# sr_lights.net
KiCad netlist of a schematic drawn in EAGLE
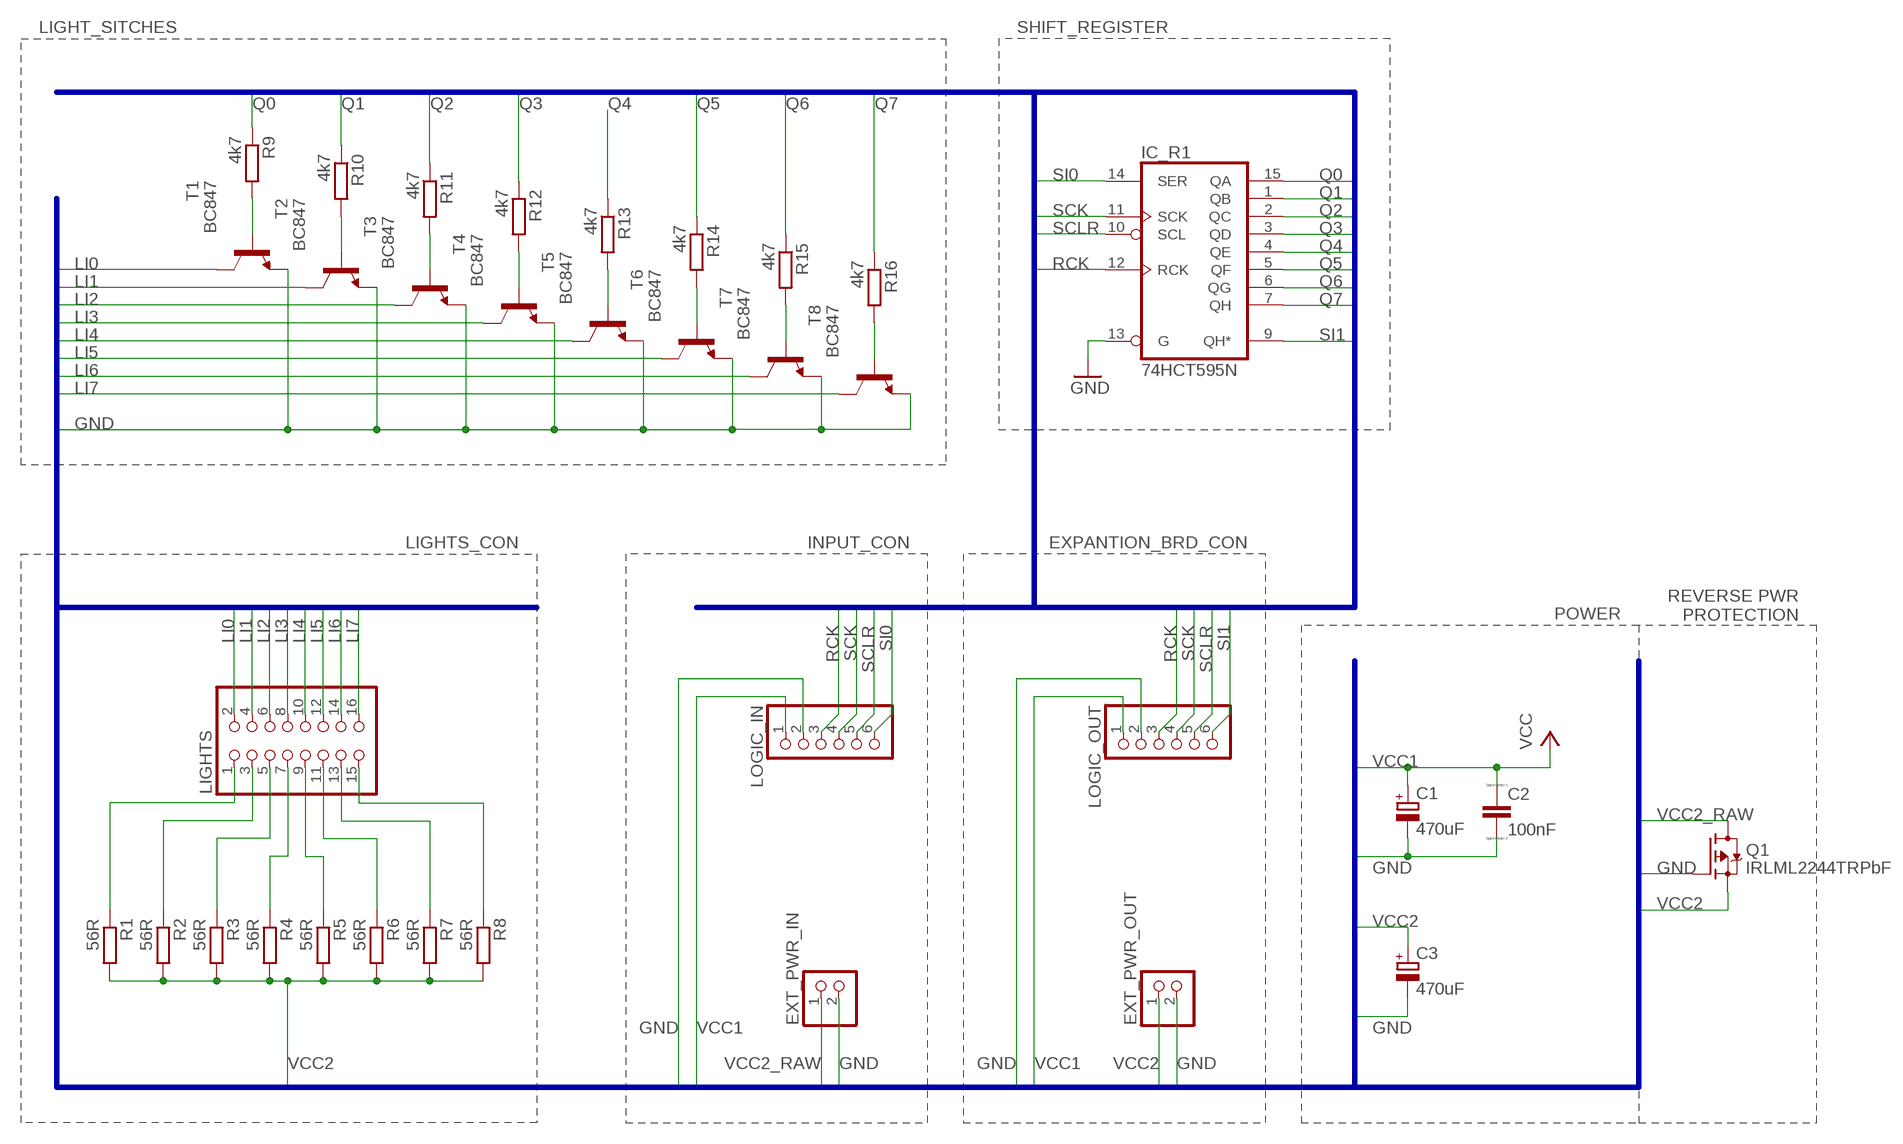
[diagram p0: schematic, sheet 1]

(export (version "E")
  (design (tool "Eeschema 10.0.6"))
  (components
    (comp (ref "C1")
      (value "470uF")
      (footprint "eagle-import:TT2D6")
      (libsource (lib "eagle-import") (part "CPOL-EUTT2D6"))
    )
    (comp (ref "C2")
      (value "100nF")
      (footprint "eagle-import:C0805")
      (libsource (lib "eagle-import") (part "C"))
    )
    (comp (ref "C3")
      (value "470uF")
      (footprint "eagle-import:TT2D6")
      (libsource (lib "eagle-import") (part "CPOL-EUTT2D6"))
    )
    (comp (ref "EXT_PWR_IN")
      (value "PINHD-1X2")
      (footprint "eagle-import:1X02")
      (libsource (lib "eagle-import") (part "PINHD-1X2"))
    )
    (comp (ref "EXT_PWR_OUT")
      (value "PINHD-1X2")
      (footprint "eagle-import:1X02")
      (libsource (lib "eagle-import") (part "PINHD-1X2"))
    )
    (comp (ref "IC_R1")
      (value "74HCT595N")
      (footprint "eagle-import:DIL16")
      (libsource (lib "eagle-import") (part "74595NHCT"))
    )
    (comp (ref "LIGHTS")
      (value "PINHD-2X8")
      (footprint "eagle-import:2X08")
      (libsource (lib "eagle-import") (part "PINHD-2X8"))
    )
    (comp (ref "LOGIC_IN")
      (value "PINHD-1X6")
      (footprint "eagle-import:1X06")
      (libsource (lib "eagle-import") (part "PINHD-1X6"))
    )
    (comp (ref "LOGIC_OUT")
      (value "PINHD-1X6")
      (footprint "eagle-import:1X06")
      (libsource (lib "eagle-import") (part "PINHD-1X6"))
    )
    (comp (ref "Q1")
      (value "IRLML2244TRPbF")
      (footprint "eagle-import:SOT23")
      (libsource (lib "eagle-import") (part "MOSFET-P-SOT23"))
    )
    (comp (ref "R1")
      (value "56R")
      (footprint "eagle-import:M0805")
      (libsource (lib "eagle-import") (part "R-EU_M0805"))
    )
    (comp (ref "R2")
      (value "56R")
      (footprint "eagle-import:M0805")
      (libsource (lib "eagle-import") (part "R-EU_M0805"))
    )
    (comp (ref "R3")
      (value "56R")
      (footprint "eagle-import:M0805")
      (libsource (lib "eagle-import") (part "R-EU_M0805"))
    )
    (comp (ref "R4")
      (value "56R")
      (footprint "eagle-import:M0805")
      (libsource (lib "eagle-import") (part "R-EU_M0805"))
    )
    (comp (ref "R5")
      (value "56R")
      (footprint "eagle-import:M0805")
      (libsource (lib "eagle-import") (part "R-EU_M0805"))
    )
    (comp (ref "R6")
      (value "56R")
      (footprint "eagle-import:M0805")
      (libsource (lib "eagle-import") (part "R-EU_M0805"))
    )
    (comp (ref "R7")
      (value "56R")
      (footprint "eagle-import:M0805")
      (libsource (lib "eagle-import") (part "R-EU_M0805"))
    )
    (comp (ref "R8")
      (value "56R")
      (footprint "eagle-import:M0805")
      (libsource (lib "eagle-import") (part "R-EU_M0805"))
    )
    (comp (ref "R9")
      (value "4k7")
      (footprint "eagle-import:M0805")
      (libsource (lib "eagle-import") (part "R-EU_M0805"))
    )
    (comp (ref "R10")
      (value "4k7")
      (footprint "eagle-import:M0805")
      (libsource (lib "eagle-import") (part "R-EU_M0805"))
    )
    (comp (ref "R11")
      (value "4k7")
      (footprint "eagle-import:M0805")
      (libsource (lib "eagle-import") (part "R-EU_M0805"))
    )
    (comp (ref "R12")
      (value "4k7")
      (footprint "eagle-import:M0805")
      (libsource (lib "eagle-import") (part "R-EU_M0805"))
    )
    (comp (ref "R13")
      (value "4k7")
      (footprint "eagle-import:M0805")
      (libsource (lib "eagle-import") (part "R-EU_M0805"))
    )
    (comp (ref "R14")
      (value "4k7")
      (footprint "eagle-import:M0805")
      (libsource (lib "eagle-import") (part "R-EU_M0805"))
    )
    (comp (ref "R15")
      (value "4k7")
      (footprint "eagle-import:M0805")
      (libsource (lib "eagle-import") (part "R-EU_M0805"))
    )
    (comp (ref "R16")
      (value "4k7")
      (footprint "eagle-import:M0805")
      (libsource (lib "eagle-import") (part "R-EU_M0805"))
    )
    (comp (ref "T1")
      (value "BC847")
      (footprint "eagle-import:SOT23")
      (libsource (lib "eagle-import") (part "BC847"))
    )
    (comp (ref "T2")
      (value "BC847")
      (footprint "eagle-import:SOT23")
      (libsource (lib "eagle-import") (part "BC847"))
    )
    (comp (ref "T3")
      (value "BC847")
      (footprint "eagle-import:SOT23")
      (libsource (lib "eagle-import") (part "BC847"))
    )
    (comp (ref "T4")
      (value "BC847")
      (footprint "eagle-import:SOT23")
      (libsource (lib "eagle-import") (part "BC847"))
    )
    (comp (ref "T5")
      (value "BC847")
      (footprint "eagle-import:SOT23")
      (libsource (lib "eagle-import") (part "BC847"))
    )
    (comp (ref "T6")
      (value "BC847")
      (footprint "eagle-import:SOT23")
      (libsource (lib "eagle-import") (part "BC847"))
    )
    (comp (ref "T7")
      (value "BC847")
      (footprint "eagle-import:SOT23")
      (libsource (lib "eagle-import") (part "BC847"))
    )
    (comp (ref "T8")
      (value "BC847")
      (footprint "eagle-import:SOT23")
      (libsource (lib "eagle-import") (part "BC847"))
    )
  )
  (nets
    (net (code "1") (name "/LI0") (class "Default")
      (node (ref "LIGHTS") (pin "2") (pinfunction "2_2") (pintype "passive"))
      (node (ref "T1") (pin "3") (pinfunction "C_3") (pintype "passive"))
    )
    (net (code "2") (name "/LI1") (class "Default")
      (node (ref "LIGHTS") (pin "4") (pinfunction "4_4") (pintype "passive"))
      (node (ref "T2") (pin "3") (pinfunction "C_3") (pintype "passive"))
    )
    (net (code "3") (name "/LI2") (class "Default")
      (node (ref "LIGHTS") (pin "6") (pinfunction "6_6") (pintype "passive"))
      (node (ref "T3") (pin "3") (pinfunction "C_3") (pintype "passive"))
    )
    (net (code "4") (name "/LI3") (class "Default")
      (node (ref "LIGHTS") (pin "8") (pinfunction "8_8") (pintype "passive"))
      (node (ref "T4") (pin "3") (pinfunction "C_3") (pintype "passive"))
    )
    (net (code "5") (name "/LI4") (class "Default")
      (node (ref "LIGHTS") (pin "10") (pinfunction "10_10") (pintype "passive"))
      (node (ref "T5") (pin "3") (pinfunction "C_3") (pintype "passive"))
    )
    (net (code "6") (name "/LI5") (class "Default")
      (node (ref "LIGHTS") (pin "12") (pinfunction "12_12") (pintype "passive"))
      (node (ref "T6") (pin "3") (pinfunction "C_3") (pintype "passive"))
    )
    (net (code "7") (name "/LI6") (class "Default")
      (node (ref "LIGHTS") (pin "14") (pinfunction "14_14") (pintype "passive"))
      (node (ref "T7") (pin "3") (pinfunction "C_3") (pintype "passive"))
    )
    (net (code "8") (name "/LI7") (class "Default")
      (node (ref "LIGHTS") (pin "16") (pinfunction "16_16") (pintype "passive"))
      (node (ref "T8") (pin "3") (pinfunction "C_3") (pintype "passive"))
    )
    (net (code "9") (name "/Q0") (class "Default")
      (node (ref "IC_R1") (pin "15") (pinfunction "QA_15") (pintype "tri_state"))
      (node (ref "R9") (pin "1") (pinfunction "1_1") (pintype "passive"))
    )
    (net (code "10") (name "/Q1") (class "Default")
      (node (ref "IC_R1") (pin "1") (pinfunction "QB_1") (pintype "tri_state"))
      (node (ref "R10") (pin "1") (pinfunction "1_1") (pintype "passive"))
    )
    (net (code "11") (name "/Q2") (class "Default")
      (node (ref "IC_R1") (pin "2") (pinfunction "QC_2") (pintype "tri_state"))
      (node (ref "R11") (pin "1") (pinfunction "1_1") (pintype "passive"))
    )
    (net (code "12") (name "/Q3") (class "Default")
      (node (ref "IC_R1") (pin "3") (pinfunction "QD_3") (pintype "tri_state"))
      (node (ref "R12") (pin "1") (pinfunction "1_1") (pintype "passive"))
    )
    (net (code "13") (name "/Q4") (class "Default")
      (node (ref "IC_R1") (pin "4") (pinfunction "QE_4") (pintype "tri_state"))
      (node (ref "R13") (pin "1") (pinfunction "1_1") (pintype "passive"))
    )
    (net (code "14") (name "/Q5") (class "Default")
      (node (ref "IC_R1") (pin "5") (pinfunction "QF_5") (pintype "tri_state"))
      (node (ref "R14") (pin "1") (pinfunction "1_1") (pintype "passive"))
    )
    (net (code "15") (name "/Q6") (class "Default")
      (node (ref "IC_R1") (pin "6") (pinfunction "QG_6") (pintype "tri_state"))
      (node (ref "R15") (pin "1") (pinfunction "1_1") (pintype "passive"))
    )
    (net (code "16") (name "/Q7") (class "Default")
      (node (ref "IC_R1") (pin "7") (pinfunction "QH_7") (pintype "tri_state"))
      (node (ref "R16") (pin "1") (pinfunction "1_1") (pintype "passive"))
    )
    (net (code "17") (name "/RCK") (class "Default")
      (node (ref "IC_R1") (pin "12") (pinfunction "RCK_12") (pintype "input"))
      (node (ref "LOGIC_IN") (pin "3") (pinfunction "3_3") (pintype "passive"))
      (node (ref "LOGIC_OUT") (pin "3") (pinfunction "3_3") (pintype "passive"))
    )
    (net (code "18") (name "/SCK") (class "Default")
      (node (ref "IC_R1") (pin "11") (pinfunction "SCK_11") (pintype "input"))
      (node (ref "LOGIC_IN") (pin "4") (pinfunction "4_4") (pintype "passive"))
      (node (ref "LOGIC_OUT") (pin "4") (pinfunction "4_4") (pintype "passive"))
    )
    (net (code "19") (name "/SCLR") (class "Default")
      (node (ref "IC_R1") (pin "10") (pinfunction "SCL_10") (pintype "input"))
      (node (ref "LOGIC_IN") (pin "5") (pinfunction "5_5") (pintype "passive"))
      (node (ref "LOGIC_OUT") (pin "5") (pinfunction "5_5") (pintype "passive"))
    )
    (net (code "20") (name "/SI0") (class "Default")
      (node (ref "IC_R1") (pin "14") (pinfunction "SER_14") (pintype "input"))
      (node (ref "LOGIC_IN") (pin "6") (pinfunction "6_6") (pintype "passive"))
    )
    (net (code "21") (name "/SI1") (class "Default")
      (node (ref "IC_R1") (pin "9") (pinfunction "QH*_9") (pintype "tri_state"))
      (node (ref "LOGIC_OUT") (pin "6") (pinfunction "6_6") (pintype "passive"))
    )
    (net (code "22") (name "/VCC2") (class "Default")
      (node (ref "C3") (pin "+") (pinfunction "+_+") (pintype "passive"))
      (node (ref "EXT_PWR_OUT") (pin "1") (pinfunction "1_1") (pintype "passive"))
      (node (ref "Q1") (pin "2") (pinfunction "S_2") (pintype "passive"))
      (node (ref "R1") (pin "2") (pinfunction "2_2") (pintype "passive"))
      (node (ref "R2") (pin "2") (pinfunction "2_2") (pintype "passive"))
      (node (ref "R3") (pin "2") (pinfunction "2_2") (pintype "passive"))
      (node (ref "R4") (pin "2") (pinfunction "2_2") (pintype "passive"))
      (node (ref "R5") (pin "2") (pinfunction "2_2") (pintype "passive"))
      (node (ref "R6") (pin "2") (pinfunction "2_2") (pintype "passive"))
      (node (ref "R7") (pin "2") (pinfunction "2_2") (pintype "passive"))
      (node (ref "R8") (pin "2") (pinfunction "2_2") (pintype "passive"))
    )
    (net (code "23") (name "/VCC2_RAW") (class "Default")
      (node (ref "EXT_PWR_IN") (pin "1") (pinfunction "1_1") (pintype "passive"))
      (node (ref "Q1") (pin "3") (pinfunction "D_3") (pintype "passive"))
    )
    (net (code "24") (name "GND") (class "Default")
      (node (ref "C1") (pin "-") (pinfunction "-_-") (pintype "passive"))
      (node (ref "C2") (pin "2") (pinfunction "2_2") (pintype "passive"))
      (node (ref "C3") (pin "-") (pinfunction "-_-") (pintype "passive"))
      (node (ref "EXT_PWR_IN") (pin "2") (pinfunction "2_2") (pintype "passive"))
      (node (ref "EXT_PWR_OUT") (pin "2") (pinfunction "2_2") (pintype "passive"))
      (node (ref "IC_R1") (pin "13") (pinfunction "G_13") (pintype "input"))
      (node (ref "LOGIC_IN") (pin "2") (pinfunction "2_2") (pintype "passive"))
      (node (ref "LOGIC_OUT") (pin "2") (pinfunction "2_2") (pintype "passive"))
      (node (ref "Q1") (pin "1") (pinfunction "G_1") (pintype "passive"))
      (node (ref "T1") (pin "2") (pinfunction "E_2") (pintype "passive"))
      (node (ref "T2") (pin "2") (pinfunction "E_2") (pintype "passive"))
      (node (ref "T3") (pin "2") (pinfunction "E_2") (pintype "passive"))
      (node (ref "T4") (pin "2") (pinfunction "E_2") (pintype "passive"))
      (node (ref "T5") (pin "2") (pinfunction "E_2") (pintype "passive"))
      (node (ref "T6") (pin "2") (pinfunction "E_2") (pintype "passive"))
      (node (ref "T7") (pin "2") (pinfunction "E_2") (pintype "passive"))
      (node (ref "T8") (pin "2") (pinfunction "E_2") (pintype "passive"))
    )
    (net (code "25") (name "Net-(LIGHTS-Pad1)") (class "Default")
      (node (ref "LIGHTS") (pin "1") (pinfunction "1_1") (pintype "passive"))
      (node (ref "R1") (pin "1") (pinfunction "1_1") (pintype "passive"))
    )
    (net (code "26") (name "Net-(LIGHTS-Pad3)") (class "Default")
      (node (ref "LIGHTS") (pin "3") (pinfunction "3_3") (pintype "passive"))
      (node (ref "R2") (pin "1") (pinfunction "1_1") (pintype "passive"))
    )
    (net (code "27") (name "Net-(LIGHTS-Pad5)") (class "Default")
      (node (ref "LIGHTS") (pin "5") (pinfunction "5_5") (pintype "passive"))
      (node (ref "R3") (pin "1") (pinfunction "1_1") (pintype "passive"))
    )
    (net (code "28") (name "Net-(LIGHTS-Pad7)") (class "Default")
      (node (ref "LIGHTS") (pin "7") (pinfunction "7_7") (pintype "passive"))
      (node (ref "R4") (pin "1") (pinfunction "1_1") (pintype "passive"))
    )
    (net (code "29") (name "Net-(LIGHTS-Pad9)") (class "Default")
      (node (ref "LIGHTS") (pin "9") (pinfunction "9_9") (pintype "passive"))
      (node (ref "R5") (pin "1") (pinfunction "1_1") (pintype "passive"))
    )
    (net (code "30") (name "Net-(LIGHTS-Pad11)") (class "Default")
      (node (ref "LIGHTS") (pin "11") (pinfunction "11_11") (pintype "passive"))
      (node (ref "R6") (pin "1") (pinfunction "1_1") (pintype "passive"))
    )
    (net (code "31") (name "Net-(LIGHTS-Pad13)") (class "Default")
      (node (ref "LIGHTS") (pin "13") (pinfunction "13_13") (pintype "passive"))
      (node (ref "R7") (pin "1") (pinfunction "1_1") (pintype "passive"))
    )
    (net (code "32") (name "Net-(LIGHTS-Pad15)") (class "Default")
      (node (ref "LIGHTS") (pin "15") (pinfunction "15_15") (pintype "passive"))
      (node (ref "R8") (pin "1") (pinfunction "1_1") (pintype "passive"))
    )
    (net (code "33") (name "Net-(T1-B)") (class "Default")
      (node (ref "R9") (pin "2") (pinfunction "2_2") (pintype "passive"))
      (node (ref "T1") (pin "1") (pinfunction "B_1") (pintype "passive"))
    )
    (net (code "34") (name "Net-(T2-B)") (class "Default")
      (node (ref "R10") (pin "2") (pinfunction "2_2") (pintype "passive"))
      (node (ref "T2") (pin "1") (pinfunction "B_1") (pintype "passive"))
    )
    (net (code "35") (name "Net-(T3-B)") (class "Default")
      (node (ref "R11") (pin "2") (pinfunction "2_2") (pintype "passive"))
      (node (ref "T3") (pin "1") (pinfunction "B_1") (pintype "passive"))
    )
    (net (code "36") (name "Net-(T4-B)") (class "Default")
      (node (ref "R12") (pin "2") (pinfunction "2_2") (pintype "passive"))
      (node (ref "T4") (pin "1") (pinfunction "B_1") (pintype "passive"))
    )
    (net (code "37") (name "Net-(T5-B)") (class "Default")
      (node (ref "R13") (pin "2") (pinfunction "2_2") (pintype "passive"))
      (node (ref "T5") (pin "1") (pinfunction "B_1") (pintype "passive"))
    )
    (net (code "38") (name "Net-(T6-B)") (class "Default")
      (node (ref "R14") (pin "2") (pinfunction "2_2") (pintype "passive"))
      (node (ref "T6") (pin "1") (pinfunction "B_1") (pintype "passive"))
    )
    (net (code "39") (name "Net-(T7-B)") (class "Default")
      (node (ref "R15") (pin "2") (pinfunction "2_2") (pintype "passive"))
      (node (ref "T7") (pin "1") (pinfunction "B_1") (pintype "passive"))
    )
    (net (code "40") (name "Net-(T8-B)") (class "Default")
      (node (ref "R16") (pin "2") (pinfunction "2_2") (pintype "passive"))
      (node (ref "T8") (pin "1") (pinfunction "B_1") (pintype "passive"))
    )
    (net (code "41") (name "VCC") (class "Default")
      (node (ref "C1") (pin "+") (pinfunction "+_+") (pintype "passive"))
      (node (ref "C2") (pin "1") (pinfunction "1_1") (pintype "passive"))
      (node (ref "LOGIC_IN") (pin "1") (pinfunction "1_1") (pintype "passive"))
      (node (ref "LOGIC_OUT") (pin "1") (pinfunction "1_1") (pintype "passive"))
    )
  )
)
